# RC_Ckt.net
KiCad netlist of a schematic drawn in Altium Designer
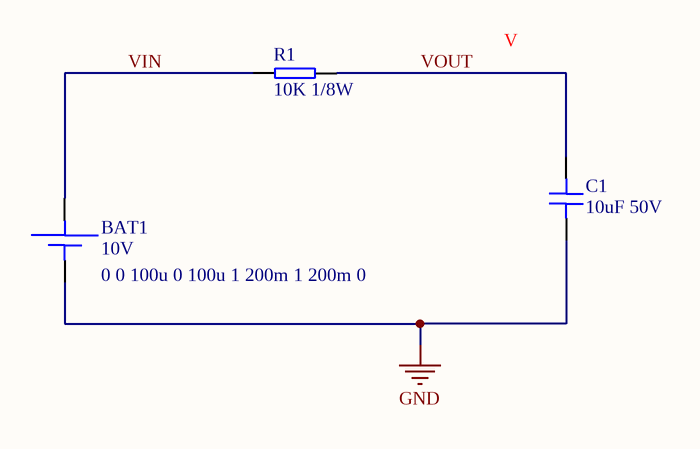
[diagram p0: RC Ckt.SchDoc]

(export (version "E")
  (design (tool "Eeschema 10.0.6"))
  (components
    (comp (ref "BAT1")
      (value "10V")
      (description "GENERIC DC SOURCE FOR SIMULATION")
      (fields (field (name "TIME-VALUE PAIRS") "0 0 100u 0 100u 1 200m 1 200m 0"))
      (libsource (lib "Daagno") (part "DC SOURCE"))
    )
    (comp (ref "C1")
      (value "10uF 50V")
      (description "CERAMIC CAPACITOR 10uF 50V 5% -55C TO 125C SMD 0805")
      (libsource (lib "Daagno") (part "CAP 10uF 50V SMD 0805"))
    )
    (comp (ref "R1")
      (value "10K 1/8W")
      (description "CHIP RESISTOR 10K 1/8W 5% -55C TO 125C SMD 0805")
      (libsource (lib "Daagno") (part "RES 10K 1/8W SMD 0805"))
    )
  )
  (nets
    (net (code "1") (name "/VIN") (class "Default")
      (node (ref "BAT1") (pin "1") (pinfunction "1_1") (pintype "passive"))
      (node (ref "R1") (pin "1") (pinfunction "1_1") (pintype "passive"))
    )
    (net (code "2") (name "/VOUT") (class "Default")
      (node (ref "C1") (pin "1") (pinfunction "1_1") (pintype "passive"))
      (node (ref "R1") (pin "2") (pinfunction "2_2") (pintype "passive"))
    )
    (net (code "3") (name "GND") (class "Default")
      (node (ref "BAT1") (pin "2") (pinfunction "2_2") (pintype "passive"))
      (node (ref "C1") (pin "2") (pinfunction "2_2") (pintype "passive"))
    )
  )
)
